# BMW_testboard.net
KiCad netlist of a schematic drawn in EAGLE
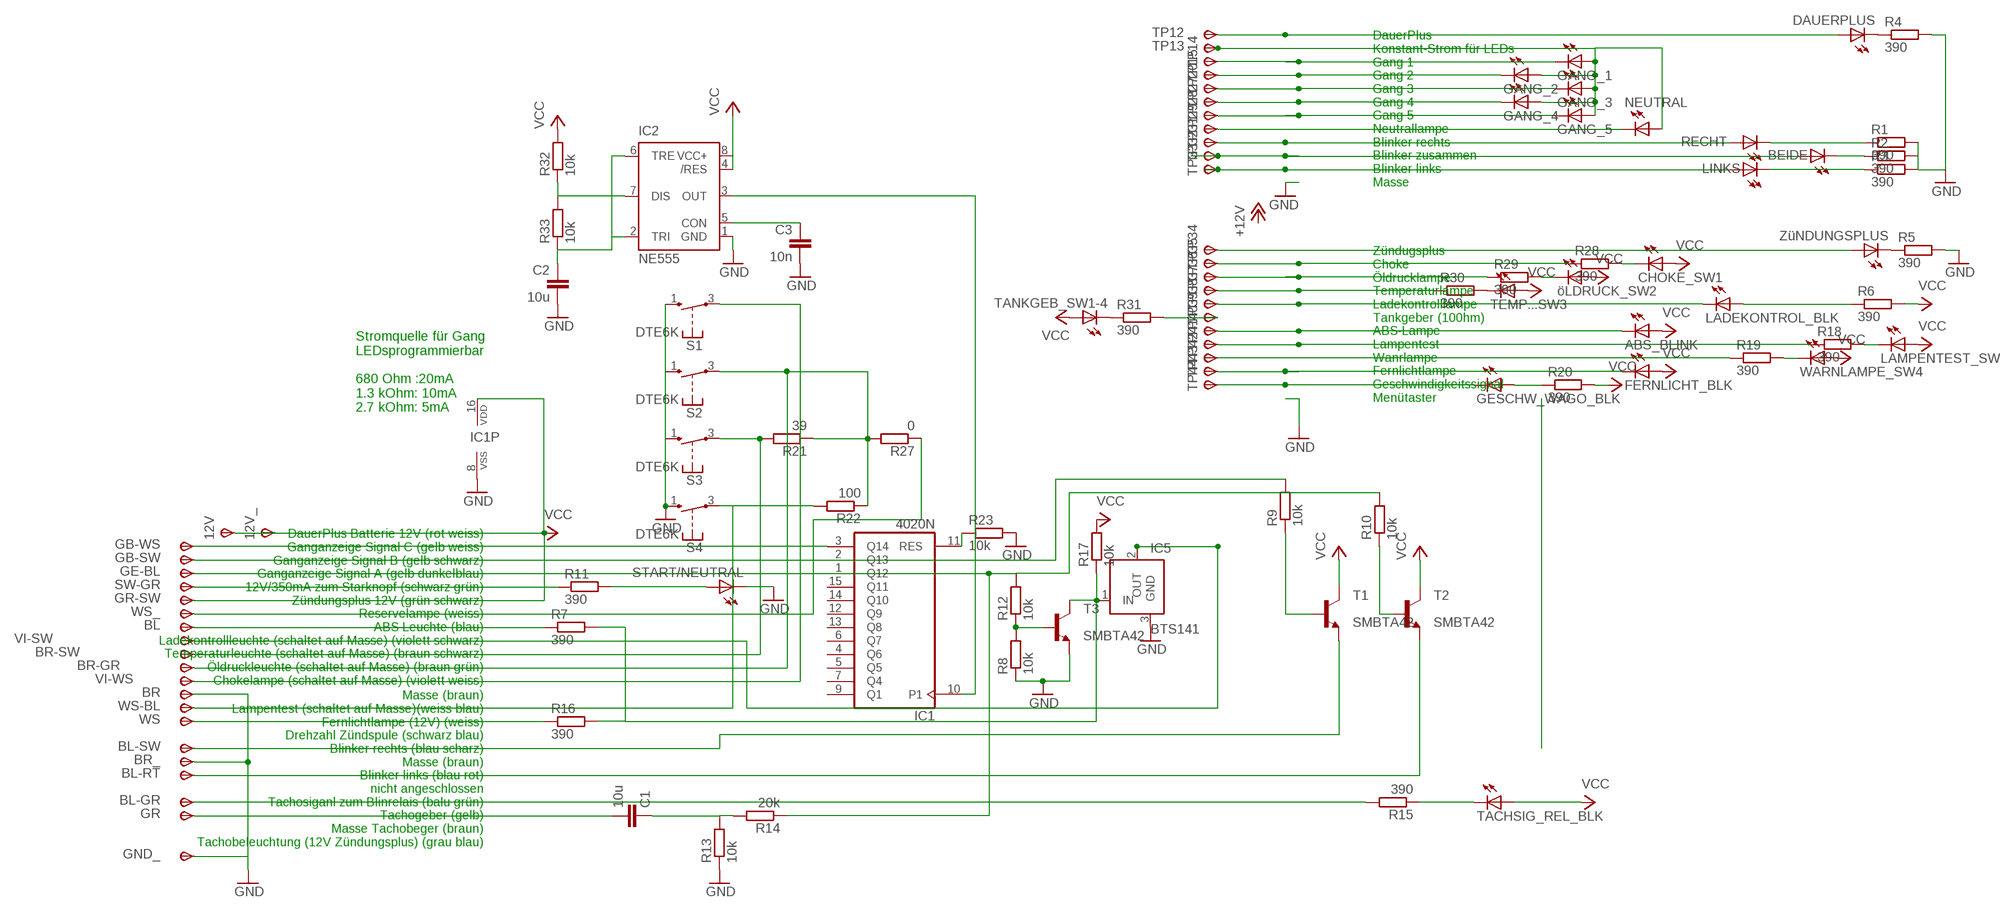
[diagram p0: schematic, sheet 1]

(export (version "E")
  (design (tool "Eeschema 10.0.6"))
  (components
    (comp (ref "12V")
      (value "TPSPAD1-1.5MM")
      (footprint "eagle-import:P1-13")
      (libsource (lib "eagle-import") (part "TPSPAD1-1.5MM"))
    )
    (comp (ref "12V_")
      (value "TPSPAD1-1.5MM")
      (footprint "eagle-import:P1-13")
      (libsource (lib "eagle-import") (part "TPSPAD1-1.5MM"))
    )
    (comp (ref "ABS_BLINK")
      (value "TLLY4400")
      (footprint "eagle-import:LED3MM")
      (fields (field (name "MF") "VISHAY SEMICONDUCTOR"))
      (libsource (lib "eagle-import") (part "TLLY4400"))
    )
    (comp (ref "BEIDE")
      (value "TLLY4400")
      (footprint "eagle-import:LED3MM")
      (fields (field (name "MF") "VISHAY SEMICONDUCTOR"))
      (libsource (lib "eagle-import") (part "TLLY4400"))
    )
    (comp (ref "BL")
      (value "TPSPAD1-1.5MM")
      (footprint "eagle-import:P1-13")
      (libsource (lib "eagle-import") (part "TPSPAD1-1.5MM"))
    )
    (comp (ref "BL-GR")
      (value "TPSPAD1-1.5MM")
      (footprint "eagle-import:P1-13")
      (libsource (lib "eagle-import") (part "TPSPAD1-1.5MM"))
    )
    (comp (ref "BL-RT")
      (value "TPSPAD1-1.5MM")
      (footprint "eagle-import:P1-13")
      (libsource (lib "eagle-import") (part "TPSPAD1-1.5MM"))
    )
    (comp (ref "BL-SW")
      (value "TPSPAD1-1.5MM")
      (footprint "eagle-import:P1-13")
      (libsource (lib "eagle-import") (part "TPSPAD1-1.5MM"))
    )
    (comp (ref "BR")
      (value "TPSPAD1-1.5MM")
      (footprint "eagle-import:P1-13")
      (libsource (lib "eagle-import") (part "TPSPAD1-1.5MM"))
    )
    (comp (ref "BR-GR")
      (value "TPSPAD1-1.5MM")
      (footprint "eagle-import:P1-13")
      (libsource (lib "eagle-import") (part "TPSPAD1-1.5MM"))
    )
    (comp (ref "BR-SW")
      (value "TPSPAD1-1.5MM")
      (footprint "eagle-import:P1-13")
      (libsource (lib "eagle-import") (part "TPSPAD1-1.5MM"))
    )
    (comp (ref "BR_")
      (value "TPSPAD1-1.5MM")
      (footprint "eagle-import:P1-13")
      (libsource (lib "eagle-import") (part "TPSPAD1-1.5MM"))
    )
    (comp (ref "C1")
      (value "10u")
      (footprint "eagle-import:C025-024X044")
      (libsource (lib "eagle-import") (part "C-EU025-024X044"))
    )
    (comp (ref "C2")
      (value "10u")
      (footprint "eagle-import:C025-024X044")
      (libsource (lib "eagle-import") (part "C-EU025-024X044"))
    )
    (comp (ref "C3")
      (value "10n")
      (footprint "eagle-import:C025-024X044")
      (libsource (lib "eagle-import") (part "C-EU025-024X044"))
    )
    (comp (ref "CHOKE_SW1")
      (value "TLLY4400")
      (footprint "eagle-import:LED3MM")
      (fields (field (name "MF") "VISHAY SEMICONDUCTOR"))
      (libsource (lib "eagle-import") (part "TLLY4400"))
    )
    (comp (ref "DAUERPLUS")
      (value "TLLY4400")
      (footprint "eagle-import:LED3MM")
      (fields (field (name "MF") "VISHAY SEMICONDUCTOR"))
      (libsource (lib "eagle-import") (part "TLLY4400"))
    )
    (comp (ref "FERNLICHT_BLK")
      (value "TLLY4400")
      (footprint "eagle-import:LED3MM")
      (fields (field (name "MF") "VISHAY SEMICONDUCTOR"))
      (libsource (lib "eagle-import") (part "TLLY4400"))
    )
    (comp (ref "GANG_1")
      (value "TLLY4400")
      (footprint "eagle-import:LED3MM")
      (fields (field (name "MF") "VISHAY SEMICONDUCTOR"))
      (libsource (lib "eagle-import") (part "TLLY4400"))
    )
    (comp (ref "GANG_2")
      (value "TLLY4400")
      (footprint "eagle-import:LED3MM")
      (fields (field (name "MF") "VISHAY SEMICONDUCTOR"))
      (libsource (lib "eagle-import") (part "TLLY4400"))
    )
    (comp (ref "GANG_3")
      (value "TLLY4400")
      (footprint "eagle-import:LED3MM")
      (fields (field (name "MF") "VISHAY SEMICONDUCTOR"))
      (libsource (lib "eagle-import") (part "TLLY4400"))
    )
    (comp (ref "GANG_4")
      (value "TLLY4400")
      (footprint "eagle-import:LED3MM")
      (fields (field (name "MF") "VISHAY SEMICONDUCTOR"))
      (libsource (lib "eagle-import") (part "TLLY4400"))
    )
    (comp (ref "GANG_5")
      (value "TLLY4400")
      (footprint "eagle-import:LED3MM")
      (fields (field (name "MF") "VISHAY SEMICONDUCTOR"))
      (libsource (lib "eagle-import") (part "TLLY4400"))
    )
    (comp (ref "GB-SW")
      (value "TPSPAD1-1.5MM")
      (footprint "eagle-import:P1-13")
      (libsource (lib "eagle-import") (part "TPSPAD1-1.5MM"))
    )
    (comp (ref "GB-WS")
      (value "TPSPAD1-1.5MM")
      (footprint "eagle-import:P1-13")
      (libsource (lib "eagle-import") (part "TPSPAD1-1.5MM"))
    )
    (comp (ref "GE-BL")
      (value "TPSPAD1-1.5MM")
      (footprint "eagle-import:P1-13")
      (libsource (lib "eagle-import") (part "TPSPAD1-1.5MM"))
    )
    (comp (ref "GESCHW_WAGO_BLK")
      (value "TLLY4400")
      (footprint "eagle-import:LED3MM")
      (fields (field (name "MF") "VISHAY SEMICONDUCTOR"))
      (libsource (lib "eagle-import") (part "TLLY4400"))
    )
    (comp (ref "GND_")
      (value "TPSPAD1-1.5MM")
      (footprint "eagle-import:P1-13")
      (libsource (lib "eagle-import") (part "TPSPAD1-1.5MM"))
    )
    (comp (ref "GR")
      (value "TPSPAD1-1.5MM")
      (footprint "eagle-import:P1-13")
      (libsource (lib "eagle-import") (part "TPSPAD1-1.5MM"))
    )
    (comp (ref "GR-SW")
      (value "TPSPAD1-1.5MM")
      (footprint "eagle-import:P1-13")
      (libsource (lib "eagle-import") (part "TPSPAD1-1.5MM"))
    )
    (comp (ref "IC1")
      (value "4020N")
      (footprint "eagle-import:DIL16")
      (libsource (lib "eagle-import") (part "4020N"))
    )
    (comp (ref "IC2")
      (value "NE555")
      (footprint "eagle-import:DIL-08")
      (fields (field (name "MF") "Arrow Electronics") (field (name "MPN") "NE555N"))
      (libsource (lib "eagle-import") (part "NE555"))
    )
    (comp (ref "IC5")
      (value "BTS141")
      (footprint "eagle-import:TO220-3-45")
      (libsource (lib "eagle-import") (part "BTS141"))
    )
    (comp (ref "LADEKONTROL_BLK")
      (value "TLLY4400")
      (footprint "eagle-import:LED3MM")
      (fields (field (name "MF") "VISHAY SEMICONDUCTOR"))
      (libsource (lib "eagle-import") (part "TLLY4400"))
    )
    (comp (ref "LAMPENTEST_SW4")
      (value "TLLY4400")
      (footprint "eagle-import:LED3MM")
      (fields (field (name "MF") "VISHAY SEMICONDUCTOR"))
      (libsource (lib "eagle-import") (part "TLLY4400"))
    )
    (comp (ref "LINKS")
      (value "TLLY4400")
      (footprint "eagle-import:LED3MM")
      (fields (field (name "MF") "VISHAY SEMICONDUCTOR"))
      (libsource (lib "eagle-import") (part "TLLY4400"))
    )
    (comp (ref "NEUTRAL")
      (value "TLLY4400")
      (footprint "eagle-import:LED3MM")
      (fields (field (name "MF") "VISHAY SEMICONDUCTOR"))
      (libsource (lib "eagle-import") (part "TLLY4400"))
    )
    (comp (ref "R1")
      (value "390")
      (footprint "eagle-import:R0805")
      (libsource (lib "eagle-import") (part "R-EU_R0805"))
    )
    (comp (ref "R2")
      (value "390")
      (footprint "eagle-import:R0805")
      (libsource (lib "eagle-import") (part "R-EU_R0805"))
    )
    (comp (ref "R3")
      (value "390")
      (footprint "eagle-import:R0805")
      (libsource (lib "eagle-import") (part "R-EU_R0805"))
    )
    (comp (ref "R4")
      (value "390")
      (footprint "eagle-import:R0805")
      (libsource (lib "eagle-import") (part "R-EU_R0805"))
    )
    (comp (ref "R5")
      (value "390")
      (footprint "eagle-import:R0805")
      (libsource (lib "eagle-import") (part "R-EU_R0805"))
    )
    (comp (ref "R6")
      (value "390")
      (footprint "eagle-import:R0805")
      (libsource (lib "eagle-import") (part "R-EU_R0805"))
    )
    (comp (ref "R7")
      (value "390")
      (footprint "eagle-import:R0805")
      (libsource (lib "eagle-import") (part "R-EU_R0805"))
    )
    (comp (ref "R8")
      (value "10k")
      (footprint "eagle-import:R0805")
      (libsource (lib "eagle-import") (part "R-EU_R0805"))
    )
    (comp (ref "R9")
      (value "10k")
      (footprint "eagle-import:R0805")
      (libsource (lib "eagle-import") (part "R-EU_R0805"))
    )
    (comp (ref "R10")
      (value "10k")
      (footprint "eagle-import:R0805")
      (libsource (lib "eagle-import") (part "R-EU_R0805"))
    )
    (comp (ref "R11")
      (value "390")
      (footprint "eagle-import:R0805")
      (libsource (lib "eagle-import") (part "R-EU_R0805"))
    )
    (comp (ref "R12")
      (value "10k")
      (footprint "eagle-import:R0805")
      (libsource (lib "eagle-import") (part "R-EU_R0805"))
    )
    (comp (ref "R13")
      (value "10k")
      (footprint "eagle-import:0207_12")
      (libsource (lib "eagle-import") (part "R-EU_0207/12"))
    )
    (comp (ref "R14")
      (value "20k")
      (footprint "eagle-import:0207_12")
      (libsource (lib "eagle-import") (part "R-EU_0207/12"))
    )
    (comp (ref "R15")
      (value "390")
      (footprint "eagle-import:R0805")
      (libsource (lib "eagle-import") (part "R-EU_R0805"))
    )
    (comp (ref "R16")
      (value "390")
      (footprint "eagle-import:R0805")
      (libsource (lib "eagle-import") (part "R-EU_R0805"))
    )
    (comp (ref "R17")
      (value "10k")
      (footprint "eagle-import:R0805")
      (libsource (lib "eagle-import") (part "R-EU_R0805"))
    )
    (comp (ref "R18")
      (value "390")
      (footprint "eagle-import:R0805")
      (libsource (lib "eagle-import") (part "R-EU_R0805"))
    )
    (comp (ref "R19")
      (value "390")
      (footprint "eagle-import:R0805")
      (libsource (lib "eagle-import") (part "R-EU_R0805"))
    )
    (comp (ref "R20")
      (value "390")
      (footprint "eagle-import:R0805")
      (libsource (lib "eagle-import") (part "R-EU_R0805"))
    )
    (comp (ref "R21")
      (value "39")
      (footprint "eagle-import:0207_12")
      (libsource (lib "eagle-import") (part "R-EU_0207/12"))
    )
    (comp (ref "R22")
      (value "100")
      (footprint "eagle-import:0207_12")
      (libsource (lib "eagle-import") (part "R-EU_0207/12"))
    )
    (comp (ref "R23")
      (value "10k")
      (footprint "eagle-import:R0805")
      (libsource (lib "eagle-import") (part "R-EU_R0805"))
    )
    (comp (ref "R27")
      (value "0")
      (footprint "eagle-import:0207_12")
      (libsource (lib "eagle-import") (part "R-EU_0207/12"))
    )
    (comp (ref "R28")
      (value "390")
      (footprint "eagle-import:R0805")
      (libsource (lib "eagle-import") (part "R-EU_R0805"))
    )
    (comp (ref "R29")
      (value "390")
      (footprint "eagle-import:R0805")
      (libsource (lib "eagle-import") (part "R-EU_R0805"))
    )
    (comp (ref "R30")
      (value "390")
      (footprint "eagle-import:R0805")
      (libsource (lib "eagle-import") (part "R-EU_R0805"))
    )
    (comp (ref "R31")
      (value "390")
      (footprint "eagle-import:R0805")
      (libsource (lib "eagle-import") (part "R-EU_R0805"))
    )
    (comp (ref "R32")
      (value "10k")
      (footprint "eagle-import:0207_12")
      (libsource (lib "eagle-import") (part "R-EU_0207/12"))
    )
    (comp (ref "R33")
      (value "10k")
      (footprint "eagle-import:0207_15")
      (libsource (lib "eagle-import") (part "R-EU_0207/15"))
    )
    (comp (ref "RECHT")
      (value "TLLY4400")
      (footprint "eagle-import:LED3MM")
      (fields (field (name "MF") "VISHAY SEMICONDUCTOR"))
      (libsource (lib "eagle-import") (part "TLLY4400"))
    )
    (comp (ref "S1")
      (value "DTE6K")
      (footprint "eagle-import:DTE6K")
      (libsource (lib "eagle-import") (part "DTE6K"))
    )
    (comp (ref "S2")
      (value "DTE6K")
      (footprint "eagle-import:DTE6K")
      (libsource (lib "eagle-import") (part "DTE6K"))
    )
    (comp (ref "S3")
      (value "DTE6K")
      (footprint "eagle-import:DTE6K")
      (libsource (lib "eagle-import") (part "DTE6K"))
    )
    (comp (ref "S4")
      (value "DTE6K")
      (footprint "eagle-import:DTE6K")
      (libsource (lib "eagle-import") (part "DTE6K"))
    )
    (comp (ref "START/NEUTRAL")
      (value "TLLY4400")
      (footprint "eagle-import:LED3MM")
      (fields (field (name "MF") "VISHAY SEMICONDUCTOR"))
      (libsource (lib "eagle-import") (part "TLLY4400"))
    )
    (comp (ref "SW-GR")
      (value "TPSPAD1-1.5MM")
      (footprint "eagle-import:P1-13")
      (libsource (lib "eagle-import") (part "TPSPAD1-1.5MM"))
    )
    (comp (ref "T1")
      (value "MMBTA42LT1-NPN-SOT23-BEC")
      (footprint "eagle-import:SOT23-BEC")
      (fields (field (name "T") "SMBTA42"))
      (libsource (lib "eagle-import") (part "-NPN-SOT23-BECMMBTA42LT1"))
    )
    (comp (ref "T2")
      (value "MMBTA42LT1-NPN-SOT23-BEC")
      (footprint "eagle-import:SOT23-BEC")
      (fields (field (name "T") "SMBTA42"))
      (libsource (lib "eagle-import") (part "-NPN-SOT23-BECMMBTA42LT1"))
    )
    (comp (ref "T3")
      (value "MMBTA42LT1-NPN-SOT23-BEC")
      (footprint "eagle-import:SOT23-BEC")
      (fields (field (name "T") "SMBTA42"))
      (libsource (lib "eagle-import") (part "-NPN-SOT23-BECMMBTA42LT1"))
    )
    (comp (ref "TACHSIG_REL_BLK")
      (value "TLLY4400")
      (footprint "eagle-import:LED3MM")
      (fields (field (name "MF") "VISHAY SEMICONDUCTOR"))
      (libsource (lib "eagle-import") (part "TLLY4400"))
    )
    (comp (ref "TANKGEB_SW1-4")
      (value "TLLY4400")
      (footprint "eagle-import:LED3MM")
      (fields (field (name "MF") "VISHAY SEMICONDUCTOR"))
      (libsource (lib "eagle-import") (part "TLLY4400"))
    )
    (comp (ref "TEMP...SW3")
      (value "TLLY4400")
      (footprint "eagle-import:LED3MM")
      (fields (field (name "MF") "VISHAY SEMICONDUCTOR"))
      (libsource (lib "eagle-import") (part "TLLY4400"))
    )
    (comp (ref "TP12")
      (value "TPSPAD1-1.5MM")
      (footprint "eagle-import:P1-13")
      (libsource (lib "eagle-import") (part "TPSPAD1-1.5MM"))
    )
    (comp (ref "TP13")
      (value "TPSPAD1-1.5MM")
      (footprint "eagle-import:P1-13")
      (libsource (lib "eagle-import") (part "TPSPAD1-1.5MM"))
    )
    (comp (ref "TP14")
      (value "TPSPAD1-1.5MM")
      (footprint "eagle-import:P1-13")
      (libsource (lib "eagle-import") (part "TPSPAD1-1.5MM"))
    )
    (comp (ref "TP15")
      (value "TPSPAD1-1.5MM")
      (footprint "eagle-import:P1-13")
      (libsource (lib "eagle-import") (part "TPSPAD1-1.5MM"))
    )
    (comp (ref "TP20")
      (value "TPSPAD1-1.5MM")
      (footprint "eagle-import:P1-13")
      (libsource (lib "eagle-import") (part "TPSPAD1-1.5MM"))
    )
    (comp (ref "TP27")
      (value "TPSPAD1-1.5MM")
      (footprint "eagle-import:P1-13")
      (libsource (lib "eagle-import") (part "TPSPAD1-1.5MM"))
    )
    (comp (ref "TP28")
      (value "TPSPAD1-1.5MM")
      (footprint "eagle-import:P1-13")
      (libsource (lib "eagle-import") (part "TPSPAD1-1.5MM"))
    )
    (comp (ref "TP29")
      (value "TPSPAD1-1.5MM")
      (footprint "eagle-import:P1-13")
      (libsource (lib "eagle-import") (part "TPSPAD1-1.5MM"))
    )
    (comp (ref "TP31")
      (value "TPSPAD1-1.5MM")
      (footprint "eagle-import:P1-13")
      (libsource (lib "eagle-import") (part "TPSPAD1-1.5MM"))
    )
    (comp (ref "TP32")
      (value "TPSPAD1-1.5MM")
      (footprint "eagle-import:P1-13")
      (libsource (lib "eagle-import") (part "TPSPAD1-1.5MM"))
    )
    (comp (ref "TP33")
      (value "TPSPAD1-1.5MM")
      (footprint "eagle-import:P1-13")
      (libsource (lib "eagle-import") (part "TPSPAD1-1.5MM"))
    )
    (comp (ref "TP34")
      (value "TPSPAD1-1.5MM")
      (footprint "eagle-import:P1-13")
      (libsource (lib "eagle-import") (part "TPSPAD1-1.5MM"))
    )
    (comp (ref "TP35")
      (value "TPSPAD1-1.5MM")
      (footprint "eagle-import:P1-13")
      (libsource (lib "eagle-import") (part "TPSPAD1-1.5MM"))
    )
    (comp (ref "TP36")
      (value "TPSPAD1-1.5MM")
      (footprint "eagle-import:P1-13")
      (libsource (lib "eagle-import") (part "TPSPAD1-1.5MM"))
    )
    (comp (ref "TP37")
      (value "TPSPAD1-1.5MM")
      (footprint "eagle-import:P1-13")
      (libsource (lib "eagle-import") (part "TPSPAD1-1.5MM"))
    )
    (comp (ref "TP38")
      (value "TPSPAD1-1.5MM")
      (footprint "eagle-import:P1-13")
      (libsource (lib "eagle-import") (part "TPSPAD1-1.5MM"))
    )
    (comp (ref "TP39")
      (value "TPSPAD1-1.5MM")
      (footprint "eagle-import:P1-13")
      (libsource (lib "eagle-import") (part "TPSPAD1-1.5MM"))
    )
    (comp (ref "TP40")
      (value "TPSPAD1-1.5MM")
      (footprint "eagle-import:P1-13")
      (libsource (lib "eagle-import") (part "TPSPAD1-1.5MM"))
    )
    (comp (ref "TP41")
      (value "TPSPAD1-1.5MM")
      (footprint "eagle-import:P1-13")
      (libsource (lib "eagle-import") (part "TPSPAD1-1.5MM"))
    )
    (comp (ref "TP42")
      (value "TPSPAD1-1.5MM")
      (footprint "eagle-import:P1-13")
      (libsource (lib "eagle-import") (part "TPSPAD1-1.5MM"))
    )
    (comp (ref "TP43")
      (value "TPSPAD1-1.5MM")
      (footprint "eagle-import:P1-13")
      (libsource (lib "eagle-import") (part "TPSPAD1-1.5MM"))
    )
    (comp (ref "TP44")
      (value "TPSPAD1-1.5MM")
      (footprint "eagle-import:P1-13")
      (libsource (lib "eagle-import") (part "TPSPAD1-1.5MM"))
    )
    (comp (ref "VI-SW")
      (value "TPSPAD1-1.5MM")
      (footprint "eagle-import:P1-13")
      (libsource (lib "eagle-import") (part "TPSPAD1-1.5MM"))
    )
    (comp (ref "VI-WS")
      (value "TPSPAD1-1.5MM")
      (footprint "eagle-import:P1-13")
      (libsource (lib "eagle-import") (part "TPSPAD1-1.5MM"))
    )
    (comp (ref "WARNLAMPE_SW4")
      (value "TLLY4400")
      (footprint "eagle-import:LED3MM")
      (fields (field (name "MF") "VISHAY SEMICONDUCTOR"))
      (libsource (lib "eagle-import") (part "TLLY4400"))
    )
    (comp (ref "WS")
      (value "TPSPAD1-1.5MM")
      (footprint "eagle-import:P1-13")
      (libsource (lib "eagle-import") (part "TPSPAD1-1.5MM"))
    )
    (comp (ref "WS-BL")
      (value "TPSPAD1-1.5MM")
      (footprint "eagle-import:P1-13")
      (libsource (lib "eagle-import") (part "TPSPAD1-1.5MM"))
    )
    (comp (ref "WS_")
      (value "TPSPAD1-1.5MM")
      (footprint "eagle-import:P1-13")
      (libsource (lib "eagle-import") (part "TPSPAD1-1.5MM"))
    )
    (comp (ref "ZüNDUNGSPLUS")
      (value "TLLY4400")
      (footprint "eagle-import:LED3MM")
      (fields (field (name "MF") "VISHAY SEMICONDUCTOR"))
      (libsource (lib "eagle-import") (part "TLLY4400"))
    )
    (comp (ref "öLDRUCK_SW2")
      (value "TLLY4400")
      (footprint "eagle-import:LED3MM")
      (fields (field (name "MF") "VISHAY SEMICONDUCTOR"))
      (libsource (lib "eagle-import") (part "TLLY4400"))
    )
  )
  (nets
    (net (code "2") (name "GND") (class "Default")
      (node (ref "BR") (pin "TP") (pinfunction "PP_TP") (pintype "input"))
      (node (ref "BR_") (pin "TP") (pinfunction "PP_TP") (pintype "input"))
      (node (ref "C2") (pin "2") (pinfunction "2_2") (pintype "passive"))
      (node (ref "C3") (pin "2") (pinfunction "2_2") (pintype "passive"))
      (node (ref "GND_") (pin "TP") (pinfunction "PP_TP") (pintype "input"))
      (node (ref "IC1") (pin "8") (pinfunction "VSS_8") (pintype "power_in"))
      (node (ref "IC2") (pin "1") (pinfunction "GND_1") (pintype "power_in"))
      (node (ref "IC5") (pin "3") (pinfunction "GND_3") (pintype "power_in"))
      (node (ref "R1") (pin "2") (pinfunction "2_2") (pintype "passive"))
      (node (ref "R13") (pin "1") (pinfunction "1_1") (pintype "passive"))
      (node (ref "R2") (pin "2") (pinfunction "2_2") (pintype "passive"))
      (node (ref "R23") (pin "2") (pinfunction "2_2") (pintype "passive"))
      (node (ref "R3") (pin "2") (pinfunction "2_2") (pintype "passive"))
      (node (ref "R4") (pin "2") (pinfunction "2_2") (pintype "passive"))
      (node (ref "R5") (pin "2") (pinfunction "2_2") (pintype "passive"))
      (node (ref "R8") (pin "1") (pinfunction "1_1") (pintype "passive"))
      (node (ref "S1") (pin "1") (pinfunction "S_1") (pintype "passive"))
      (node (ref "S2") (pin "1") (pinfunction "S_1") (pintype "passive"))
      (node (ref "S3") (pin "1") (pinfunction "S_1") (pintype "passive"))
      (node (ref "S4") (pin "1") (pinfunction "S_1") (pintype "passive"))
      (node (ref "START/NEUTRAL") (pin "K") (pinfunction "C_K") (pintype "passive"))
      (node (ref "T3") (pin "E") (pinfunction "E_E") (pintype "passive"))
    )
    (net (code "3") (name "Net-(ABS_BLINK-C)") (class "Default")
      (node (ref "ABS_BLINK") (pin "K") (pinfunction "C_K") (pintype "passive"))
      (node (ref "TP40") (pin "TP") (pinfunction "PP_TP") (pintype "input"))
    )
    (net (code "4") (name "Net-(BEIDE-C)") (class "Default")
      (node (ref "BEIDE") (pin "K") (pinfunction "C_K") (pintype "passive"))
      (node (ref "R2") (pin "1") (pinfunction "1_1") (pintype "passive"))
    )
    (net (code "5") (name "Net-(BL-GR-PP)") (class "Default")
      (node (ref "BL-GR") (pin "TP") (pinfunction "PP_TP") (pintype "input"))
      (node (ref "R15") (pin "2") (pinfunction "2_2") (pintype "passive"))
    )
    (net (code "6") (name "Net-(BL-PP)") (class "Default")
      (node (ref "BL") (pin "TP") (pinfunction "PP_TP") (pintype "input"))
      (node (ref "R7") (pin "1") (pinfunction "1_1") (pintype "passive"))
    )
    (net (code "7") (name "Net-(BL-RT-PP)") (class "Default")
      (node (ref "BL-RT") (pin "TP") (pinfunction "PP_TP") (pintype "input"))
      (node (ref "T2") (pin "E") (pinfunction "E_E") (pintype "passive"))
    )
    (net (code "8") (name "Net-(BL-SW-PP)") (class "Default")
      (node (ref "BL-SW") (pin "TP") (pinfunction "PP_TP") (pintype "input"))
      (node (ref "T1") (pin "E") (pinfunction "E_E") (pintype "passive"))
    )
    (net (code "9") (name "Net-(BR-GR-PP)") (class "Default")
      (node (ref "BR-GR") (pin "TP") (pinfunction "PP_TP") (pintype "input"))
      (node (ref "R21") (pin "1") (pinfunction "1_1") (pintype "passive"))
      (node (ref "R22") (pin "1") (pinfunction "1_1") (pintype "passive"))
      (node (ref "R27") (pin "2") (pinfunction "2_2") (pintype "passive"))
      (node (ref "S2") (pin "3") (pinfunction "P_3") (pintype "passive"))
    )
    (net (code "10") (name "Net-(BR-SW-PP)") (class "Default")
      (node (ref "BR-SW") (pin "TP") (pinfunction "PP_TP") (pintype "input"))
      (node (ref "R21") (pin "2") (pinfunction "2_2") (pintype "passive"))
      (node (ref "S3") (pin "3") (pinfunction "P_3") (pintype "passive"))
    )
    (net (code "11") (name "Net-(C1-Pad1)") (class "Default")
      (node (ref "C1") (pin "1") (pinfunction "1_1") (pintype "passive"))
      (node (ref "R13") (pin "2") (pinfunction "2_2") (pintype "passive"))
      (node (ref "R14") (pin "2") (pinfunction "2_2") (pintype "passive"))
    )
    (net (code "12") (name "Net-(CHOKE_SW1-C)") (class "Default")
      (node (ref "CHOKE_SW1") (pin "K") (pinfunction "C_K") (pintype "passive"))
      (node (ref "R28") (pin "2") (pinfunction "2_2") (pintype "passive"))
    )
    (net (code "13") (name "Net-(DAUERPLUS-C)") (class "Default")
      (node (ref "DAUERPLUS") (pin "K") (pinfunction "C_K") (pintype "passive"))
      (node (ref "R4") (pin "1") (pinfunction "1_1") (pintype "passive"))
    )
    (net (code "14") (name "Net-(FERNLICHT_BLK-C)") (class "Default")
      (node (ref "FERNLICHT_BLK") (pin "K") (pinfunction "C_K") (pintype "passive"))
      (node (ref "TP43") (pin "TP") (pinfunction "PP_TP") (pintype "input"))
    )
    (net (code "15") (name "Net-(GANG_1-C)") (class "Default")
      (node (ref "GANG_1") (pin "K") (pinfunction "C_K") (pintype "passive"))
      (node (ref "TP14") (pin "TP") (pinfunction "PP_TP") (pintype "input"))
    )
    (net (code "16") (name "Net-(GANG_2-C)") (class "Default")
      (node (ref "GANG_2") (pin "K") (pinfunction "C_K") (pintype "passive"))
      (node (ref "TP15") (pin "TP") (pinfunction "PP_TP") (pintype "input"))
    )
    (net (code "17") (name "Net-(GANG_3-C)") (class "Default")
      (node (ref "GANG_3") (pin "K") (pinfunction "C_K") (pintype "passive"))
      (node (ref "TP20") (pin "TP") (pinfunction "PP_TP") (pintype "input"))
    )
    (net (code "18") (name "Net-(GANG_4-C)") (class "Default")
      (node (ref "GANG_4") (pin "K") (pinfunction "C_K") (pintype "passive"))
      (node (ref "TP27") (pin "TP") (pinfunction "PP_TP") (pintype "input"))
    )
    (net (code "19") (name "Net-(GANG_5-C)") (class "Default")
      (node (ref "GANG_5") (pin "K") (pinfunction "C_K") (pintype "passive"))
      (node (ref "TP28") (pin "TP") (pinfunction "PP_TP") (pintype "input"))
    )
    (net (code "20") (name "Net-(GB-SW-PP)") (class "Default")
      (node (ref "GB-SW") (pin "TP") (pinfunction "PP_TP") (pintype "input"))
      (node (ref "IC1") (pin "2") (pinfunction "Q13_2") (pintype "output"))
      (node (ref "R9") (pin "2") (pinfunction "2_2") (pintype "passive"))
    )
    (net (code "21") (name "Net-(GB-WS-PP)") (class "Default")
      (node (ref "GB-WS") (pin "TP") (pinfunction "PP_TP") (pintype "input"))
      (node (ref "IC1") (pin "3") (pinfunction "Q14_3") (pintype "output"))
    )
    (net (code "22") (name "Net-(GE-BL-PP)") (class "Default")
      (node (ref "GE-BL") (pin "TP") (pinfunction "PP_TP") (pintype "input"))
      (node (ref "IC1") (pin "1") (pinfunction "Q12_1") (pintype "output"))
      (node (ref "R10") (pin "2") (pinfunction "2_2") (pintype "passive"))
      (node (ref "R12") (pin "2") (pinfunction "2_2") (pintype "passive"))
      (node (ref "R14") (pin "1") (pinfunction "1_1") (pintype "passive"))
    )
    (net (code "23") (name "Net-(GESCHW_WAGO_BLK-C)") (class "Default")
      (node (ref "GESCHW_WAGO_BLK") (pin "K") (pinfunction "C_K") (pintype "passive"))
      (node (ref "TP44") (pin "TP") (pinfunction "PP_TP") (pintype "input"))
    )
    (net (code "24") (name "Net-(GESCHW_WAGO_BLK-PadA)") (class "Default")
      (node (ref "GESCHW_WAGO_BLK") (pin "A") (pinfunction "A_A") (pintype "passive"))
      (node (ref "R20") (pin "1") (pinfunction "1_1") (pintype "passive"))
    )
    (net (code "25") (name "Net-(GR-PP)") (class "Default")
      (node (ref "C1") (pin "2") (pinfunction "2_2") (pintype "passive"))
      (node (ref "GR") (pin "TP") (pinfunction "PP_TP") (pintype "input"))
    )
    (net (code "26") (name "Net-(IC1A-P1)") (class "Default")
      (node (ref "IC1") (pin "10") (pinfunction "P1_10") (pintype "input"))
      (node (ref "IC2") (pin "3") (pinfunction "OUT_3") (pintype "output"))
    )
    (net (code "27") (name "Net-(IC1A-RES)") (class "Default")
      (node (ref "IC1") (pin "11") (pinfunction "RES_11") (pintype "input"))
      (node (ref "R23") (pin "1") (pinfunction "1_1") (pintype "passive"))
    )
    (net (code "28") (name "Net-(IC2-CON)") (class "Default")
      (node (ref "C3") (pin "1") (pinfunction "1_1") (pintype "passive"))
      (node (ref "IC2") (pin "5") (pinfunction "CON_5") (pintype "input"))
    )
    (net (code "29") (name "Net-(IC2-DIS)") (class "Default")
      (node (ref "IC2") (pin "7") (pinfunction "DIS_7") (pintype "input"))
      (node (ref "R32") (pin "1") (pinfunction "1_1") (pintype "passive"))
      (node (ref "R33") (pin "2") (pinfunction "2_2") (pintype "passive"))
    )
    (net (code "30") (name "Net-(IC2-TRE)") (class "Default")
      (node (ref "C2") (pin "1") (pinfunction "1_1") (pintype "passive"))
      (node (ref "IC2") (pin "2") (pinfunction "TRI_2") (pintype "input"))
      (node (ref "IC2") (pin "6") (pinfunction "TRE_6") (pintype "input"))
      (node (ref "R33") (pin "1") (pinfunction "1_1") (pintype "passive"))
    )
    (net (code "31") (name "Net-(IC5-IN)") (class "Default")
      (node (ref "IC5") (pin "1") (pinfunction "IN_1") (pintype "input"))
      (node (ref "R16") (pin "2") (pinfunction "2_2") (pintype "passive"))
      (node (ref "R17") (pin "1") (pinfunction "1_1") (pintype "passive"))
      (node (ref "R7") (pin "2") (pinfunction "2_2") (pintype "passive"))
      (node (ref "T3") (pin "C") (pinfunction "C_C") (pintype "passive"))
    )
    (net (code "32") (name "Net-(IC5-OUT)") (class "Default")
      (node (ref "IC5") (pin "2") (pinfunction "OUT_2") (pintype "output"))
      (node (ref "VI-SW") (pin "TP") (pinfunction "PP_TP") (pintype "input"))
    )
    (net (code "33") (name "Net-(LADEKONTROL_BLK-C)") (class "Default")
      (node (ref "LADEKONTROL_BLK") (pin "K") (pinfunction "C_K") (pintype "passive"))
      (node (ref "TP38") (pin "TP") (pinfunction "PP_TP") (pintype "input"))
    )
    (net (code "34") (name "Net-(LADEKONTROL_BLK-PadA)") (class "Default")
      (node (ref "LADEKONTROL_BLK") (pin "A") (pinfunction "A_A") (pintype "passive"))
      (node (ref "R6") (pin "1") (pinfunction "1_1") (pintype "passive"))
    )
    (net (code "35") (name "Net-(LAMPENTEST_SW4-C)") (class "Default")
      (node (ref "LAMPENTEST_SW4") (pin "K") (pinfunction "C_K") (pintype "passive"))
      (node (ref "R18") (pin "2") (pinfunction "2_2") (pintype "passive"))
    )
    (net (code "36") (name "Net-(LINKS-C)") (class "Default")
      (node (ref "LINKS") (pin "K") (pinfunction "C_K") (pintype "passive"))
      (node (ref "R3") (pin "1") (pinfunction "1_1") (pintype "passive"))
    )
    (net (code "37") (name "Net-(NEUTRAL-C)") (class "Default")
      (node (ref "NEUTRAL") (pin "K") (pinfunction "C_K") (pintype "passive"))
      (node (ref "TP29") (pin "TP") (pinfunction "PP_TP") (pintype "input"))
    )
    (net (code "38") (name "Net-(R9-Pad1)") (class "Default")
      (node (ref "R9") (pin "1") (pinfunction "1_1") (pintype "passive"))
      (node (ref "T1") (pin "B") (pinfunction "B_B") (pintype "passive"))
    )
    (net (code "39") (name "Net-(R10-Pad1)") (class "Default")
      (node (ref "R10") (pin "1") (pinfunction "1_1") (pintype "passive"))
      (node (ref "T2") (pin "B") (pinfunction "B_B") (pintype "passive"))
    )
    (net (code "40") (name "Net-(R11-Pad2)") (class "Default")
      (node (ref "R11") (pin "2") (pinfunction "2_2") (pintype "passive"))
      (node (ref "START/NEUTRAL") (pin "A") (pinfunction "A_A") (pintype "passive"))
    )
    (net (code "41") (name "Net-(R12-Pad1)") (class "Default")
      (node (ref "R12") (pin "1") (pinfunction "1_1") (pintype "passive"))
      (node (ref "R8") (pin "2") (pinfunction "2_2") (pintype "passive"))
      (node (ref "T3") (pin "B") (pinfunction "B_B") (pintype "passive"))
    )
    (net (code "42") (name "Net-(RECHT-C)") (class "Default")
      (node (ref "R1") (pin "1") (pinfunction "1_1") (pintype "passive"))
      (node (ref "RECHT") (pin "K") (pinfunction "C_K") (pintype "passive"))
    )
    (net (code "43") (name "Net-(S1-P)") (class "Default")
      (node (ref "S1") (pin "3") (pinfunction "P_3") (pintype "passive"))
      (node (ref "VI-WS") (pin "TP") (pinfunction "PP_TP") (pintype "input"))
    )
    (net (code "44") (name "Net-(S4-P)") (class "Default")
      (node (ref "R22") (pin "2") (pinfunction "2_2") (pintype "passive"))
      (node (ref "S4") (pin "3") (pinfunction "P_3") (pintype "passive"))
      (node (ref "WS-BL") (pin "TP") (pinfunction "PP_TP") (pintype "input"))
    )
    (net (code "45") (name "Net-(SW-GR-PP)") (class "Default")
      (node (ref "R11") (pin "1") (pinfunction "1_1") (pintype "passive"))
      (node (ref "SW-GR") (pin "TP") (pinfunction "PP_TP") (pintype "input"))
    )
    (net (code "46") (name "Net-(TACHSIG_REL_BLK-C)") (class "Default")
      (node (ref "R15") (pin "1") (pinfunction "1_1") (pintype "passive"))
      (node (ref "TACHSIG_REL_BLK") (pin "K") (pinfunction "C_K") (pintype "passive"))
    )
    (net (code "47") (name "Net-(TANKGEB_SW1-4-C)") (class "Default")
      (node (ref "R31") (pin "1") (pinfunction "1_1") (pintype "passive"))
      (node (ref "TANKGEB_SW1-4") (pin "K") (pinfunction "C_K") (pintype "passive"))
    )
    (net (code "48") (name "Net-(TEMP...SW3-C)") (class "Default")
      (node (ref "R30") (pin "2") (pinfunction "2_2") (pintype "passive"))
      (node (ref "TEMP...SW3") (pin "K") (pinfunction "C_K") (pintype "passive"))
    )
    (net (code "49") (name "Net-(TP12-PP)") (class "Default")
      (node (ref "DAUERPLUS") (pin "A") (pinfunction "A_A") (pintype "passive"))
      (node (ref "TP12") (pin "TP") (pinfunction "PP_TP") (pintype "input"))
    )
    (net (code "50") (name "Net-(TP13-PP)") (class "Default")
      (node (ref "GANG_1") (pin "A") (pinfunction "A_A") (pintype "passive"))
      (node (ref "GANG_2") (pin "A") (pinfunction "A_A") (pintype "passive"))
      (node (ref "GANG_3") (pin "A") (pinfunction "A_A") (pintype "passive"))
      (node (ref "GANG_4") (pin "A") (pinfunction "A_A") (pintype "passive"))
      (node (ref "GANG_5") (pin "A") (pinfunction "A_A") (pintype "passive"))
      (node (ref "NEUTRAL") (pin "A") (pinfunction "A_A") (pintype "passive"))
      (node (ref "TP13") (pin "TP") (pinfunction "PP_TP") (pintype "input"))
    )
    (net (code "51") (name "Net-(TP31-PP)") (class "Default")
      (node (ref "RECHT") (pin "A") (pinfunction "A_A") (pintype "passive"))
      (node (ref "TP31") (pin "TP") (pinfunction "PP_TP") (pintype "input"))
    )
    (net (code "52") (name "Net-(TP32-PP)") (class "Default")
      (node (ref "BEIDE") (pin "A") (pinfunction "A_A") (pintype "passive"))
      (node (ref "TP32") (pin "TP") (pinfunction "PP_TP") (pintype "input"))
    )
    (net (code "53") (name "Net-(TP33-PP)") (class "Default")
      (node (ref "LINKS") (pin "A") (pinfunction "A_A") (pintype "passive"))
      (node (ref "TP33") (pin "TP") (pinfunction "PP_TP") (pintype "input"))
    )
    (net (code "54") (name "Net-(TP34-PP)") (class "Default")
      (node (ref "TP34") (pin "TP") (pinfunction "PP_TP") (pintype "input"))
      (node (ref "ZüNDUNGSPLUS") (pin "A") (pinfunction "A_A") (pintype "passive"))
    )
    (net (code "55") (name "Net-(TP35-PP)") (class "Default")
      (node (ref "R28") (pin "1") (pinfunction "1_1") (pintype "passive"))
      (node (ref "TP35") (pin "TP") (pinfunction "PP_TP") (pintype "input"))
    )
    (net (code "56") (name "Net-(TP36-PP)") (class "Default")
      (node (ref "R29") (pin "1") (pinfunction "1_1") (pintype "passive"))
      (node (ref "TP36") (pin "TP") (pinfunction "PP_TP") (pintype "input"))
    )
    (net (code "57") (name "Net-(TP37-PP)") (class "Default")
      (node (ref "R30") (pin "1") (pinfunction "1_1") (pintype "passive"))
      (node (ref "TP37") (pin "TP") (pinfunction "PP_TP") (pintype "input"))
    )
    (net (code "58") (name "Net-(TP39-PP)") (class "Default")
      (node (ref "R31") (pin "2") (pinfunction "2_2") (pintype "passive"))
      (node (ref "TP39") (pin "TP") (pinfunction "PP_TP") (pintype "input"))
    )
    (net (code "59") (name "Net-(TP41-PP)") (class "Default")
      (node (ref "R18") (pin "1") (pinfunction "1_1") (pintype "passive"))
      (node (ref "TP41") (pin "TP") (pinfunction "PP_TP") (pintype "input"))
    )
    (net (code "60") (name "Net-(TP42-PP)") (class "Default")
      (node (ref "R19") (pin "1") (pinfunction "1_1") (pintype "passive"))
      (node (ref "TP42") (pin "TP") (pinfunction "PP_TP") (pintype "input"))
    )
    (net (code "61") (name "Net-(WARNLAMPE_SW4-C)") (class "Default")
      (node (ref "R19") (pin "2") (pinfunction "2_2") (pintype "passive"))
      (node (ref "WARNLAMPE_SW4") (pin "K") (pinfunction "C_K") (pintype "passive"))
    )
    (net (code "62") (name "Net-(WS-PP)") (class "Default")
      (node (ref "R16") (pin "1") (pinfunction "1_1") (pintype "passive"))
      (node (ref "WS") (pin "TP") (pinfunction "PP_TP") (pintype "input"))
    )
    (net (code "63") (name "Net-(WS_-PP)") (class "Default")
      (node (ref "R27") (pin "1") (pinfunction "1_1") (pintype "passive"))
      (node (ref "WS_") (pin "TP") (pinfunction "PP_TP") (pintype "input"))
    )
    (net (code "64") (name "Net-(ZüNDUNGSPLUS-C)") (class "Default")
      (node (ref "R5") (pin "1") (pinfunction "1_1") (pintype "passive"))
      (node (ref "ZüNDUNGSPLUS") (pin "K") (pinfunction "C_K") (pintype "passive"))
    )
    (net (code "65") (name "Net-(öLDRUCK_SW2-C)") (class "Default")
      (node (ref "R29") (pin "2") (pinfunction "2_2") (pintype "passive"))
      (node (ref "öLDRUCK_SW2") (pin "K") (pinfunction "C_K") (pintype "passive"))
    )
    (net (code "66") (name "VCC") (class "Default")
      (node (ref "12V") (pin "TP") (pinfunction "PP_TP") (pintype "input"))
      (node (ref "12V_") (pin "TP") (pinfunction "PP_TP") (pintype "input"))
      (node (ref "ABS_BLINK") (pin "A") (pinfunction "A_A") (pintype "passive"))
      (node (ref "CHOKE_SW1") (pin "A") (pinfunction "A_A") (pintype "passive"))
      (node (ref "FERNLICHT_BLK") (pin "A") (pinfunction "A_A") (pintype "passive"))
      (node (ref "GR-SW") (pin "TP") (pinfunction "PP_TP") (pintype "input"))
      (node (ref "IC1") (pin "16") (pinfunction "VDD_16") (pintype "power_in"))
      (node (ref "IC2") (pin "4") (pinfunction "/RES_4") (pintype "input"))
      (node (ref "IC2") (pin "8") (pinfunction "VCC+_8") (pintype "power_in"))
      (node (ref "LAMPENTEST_SW4") (pin "A") (pinfunction "A_A") (pintype "passive"))
      (node (ref "R17") (pin "2") (pinfunction "2_2") (pintype "passive"))
      (node (ref "R20") (pin "2") (pinfunction "2_2") (pintype "passive"))
      (node (ref "R32") (pin "2") (pinfunction "2_2") (pintype "passive"))
      (node (ref "R6") (pin "2") (pinfunction "2_2") (pintype "passive"))
      (node (ref "T1") (pin "C") (pinfunction "C_C") (pintype "passive"))
      (node (ref "T2") (pin "C") (pinfunction "C_C") (pintype "passive"))
      (node (ref "TACHSIG_REL_BLK") (pin "A") (pinfunction "A_A") (pintype "passive"))
      (node (ref "TANKGEB_SW1-4") (pin "A") (pinfunction "A_A") (pintype "passive"))
      (node (ref "TEMP...SW3") (pin "A") (pinfunction "A_A") (pintype "passive"))
      (node (ref "WARNLAMPE_SW4") (pin "A") (pinfunction "A_A") (pintype "passive"))
      (node (ref "öLDRUCK_SW2") (pin "A") (pinfunction "A_A") (pintype "passive"))
    )
    (net (code "67") (name "unconnected-(IC1A-Q1-Pad9)") (class "Default")
      (node (ref "IC1") (pin "9") (pinfunction "Q1_9") (pintype "output"))
    )
    (net (code "68") (name "unconnected-(IC1A-Q4-Pad7)") (class "Default")
      (node (ref "IC1") (pin "7") (pinfunction "Q4_7") (pintype "output"))
    )
    (net (code "69") (name "unconnected-(IC1A-Q5-Pad5)") (class "Default")
      (node (ref "IC1") (pin "5") (pinfunction "Q5_5") (pintype "output"))
    )
    (net (code "70") (name "unconnected-(IC1A-Q6-Pad4)") (class "Default")
      (node (ref "IC1") (pin "4") (pinfunction "Q6_4") (pintype "output"))
    )
    (net (code "71") (name "unconnected-(IC1A-Q7-Pad6)") (class "Default")
      (node (ref "IC1") (pin "6") (pinfunction "Q7_6") (pintype "output"))
    )
    (net (code "72") (name "unconnected-(IC1A-Q8-Pad13)") (class "Default")
      (node (ref "IC1") (pin "13") (pinfunction "Q8_13") (pintype "output"))
    )
    (net (code "73") (name "unconnected-(IC1A-Q9-Pad12)") (class "Default")
      (node (ref "IC1") (pin "12") (pinfunction "Q9_12") (pintype "output"))
    )
    (net (code "74") (name "unconnected-(IC1A-Q10-Pad14)") (class "Default")
      (node (ref "IC1") (pin "14") (pinfunction "Q10_14") (pintype "output"))
    )
    (net (code "75") (name "unconnected-(IC1A-Q11-Pad15)") (class "Default")
      (node (ref "IC1") (pin "15") (pinfunction "Q11_15") (pintype "output"))
    )
  )
)
